# dac.net
KiCad netlist of a schematic drawn in EAGLE
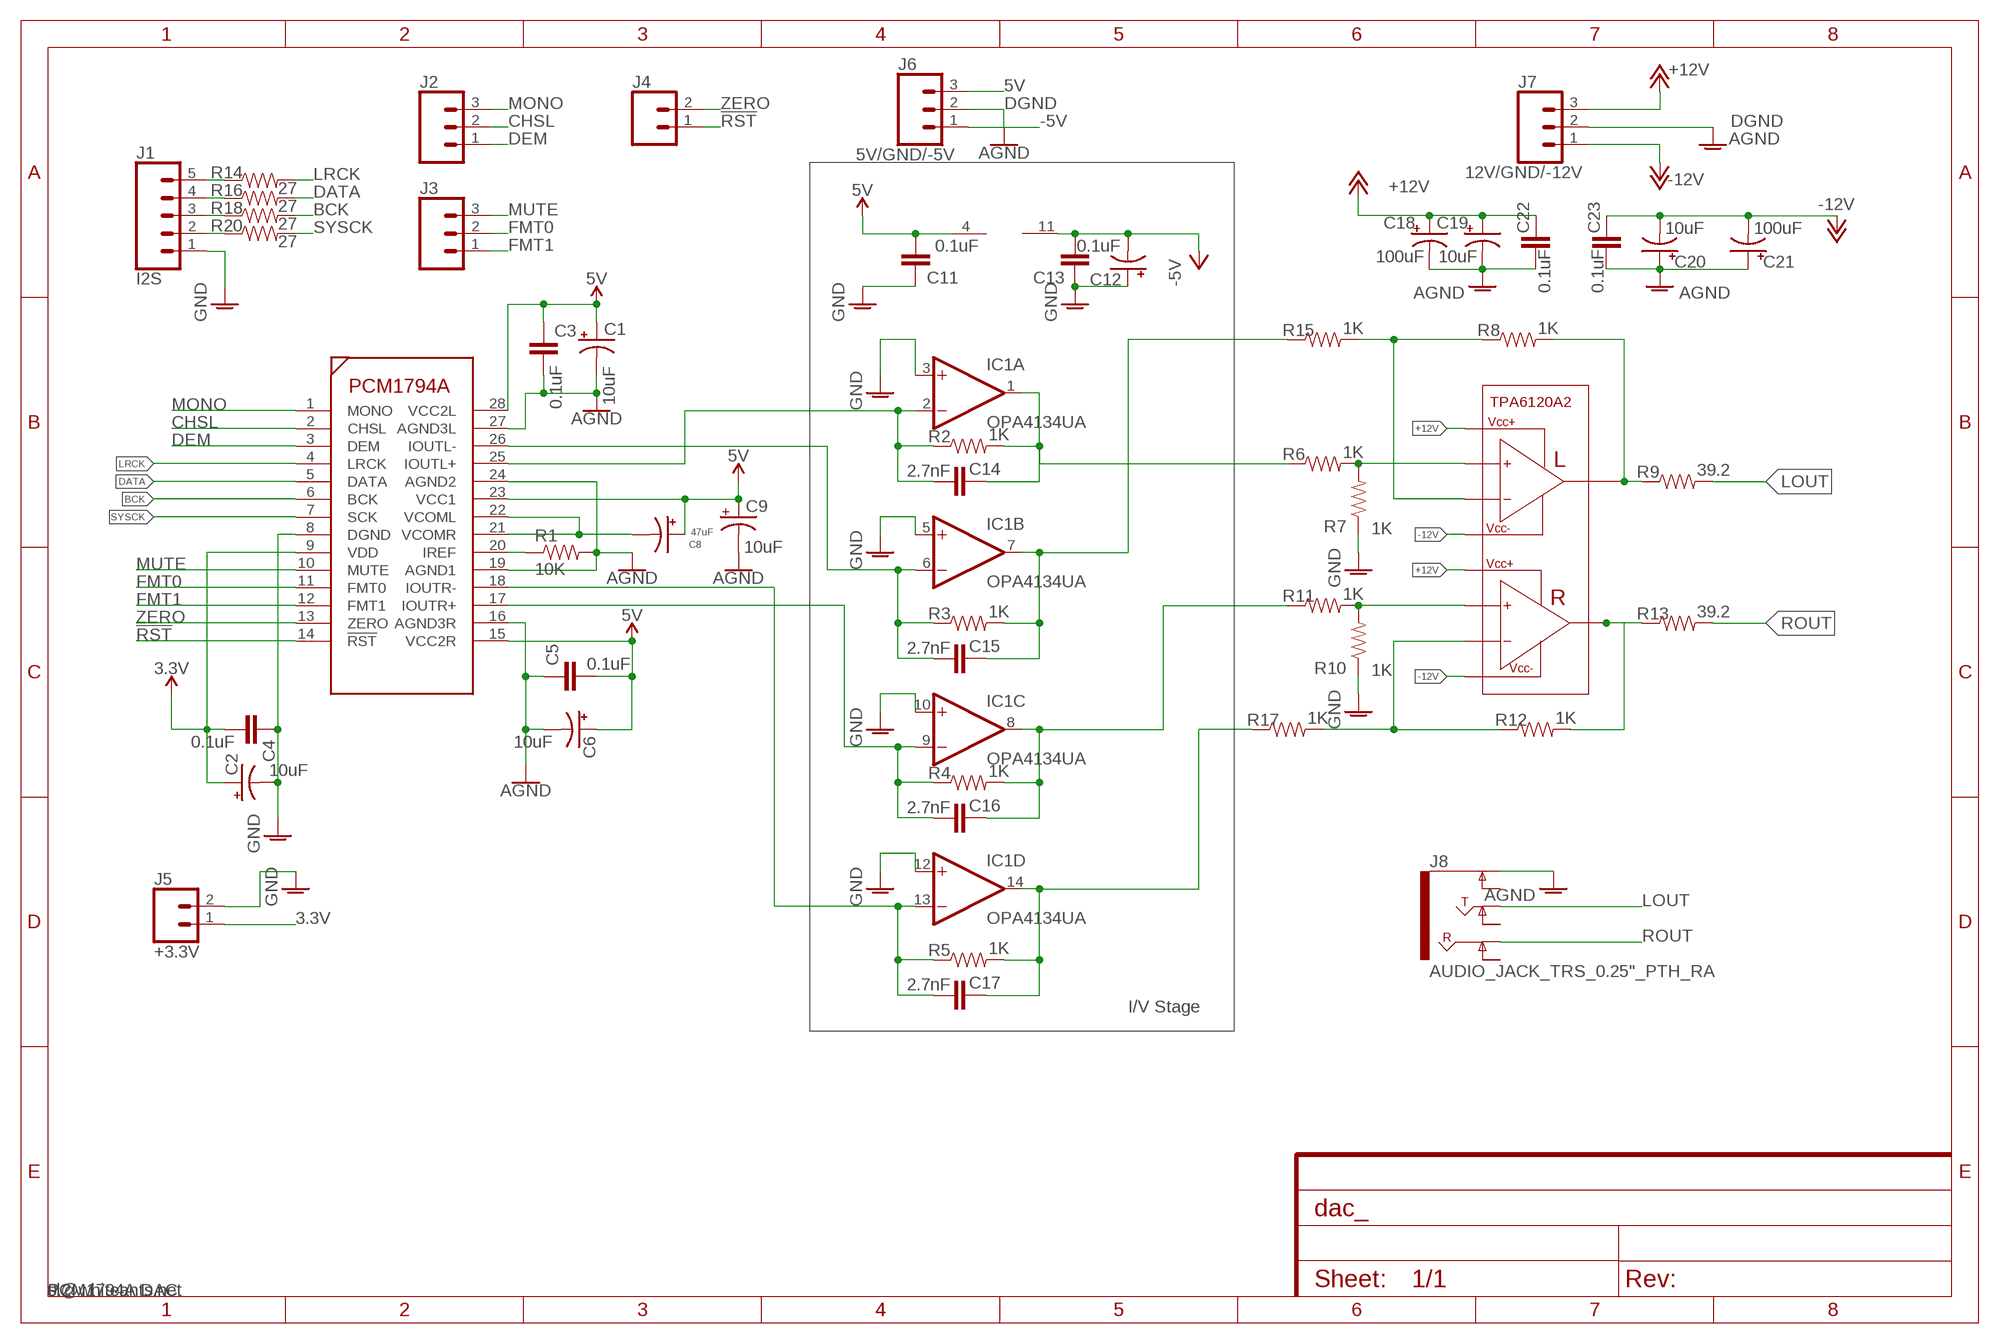
[diagram p0: schematic, sheet 1]

(export (version "E")
  (design (tool "Eeschema 10.0.6"))
  (components
    (comp (ref "C1")
      (value "10uF")
      (footprint "eagle-import:CPOL-RADIAL-100UF-25V")
      (libsource (lib "eagle-import") (part "CAP_POLPTH1"))
    )
    (comp (ref "C2")
      (value "10uF")
      (footprint "eagle-import:CPOL-RADIAL-100UF-25V")
      (libsource (lib "eagle-import") (part "CAP_POLPTH1"))
    )
    (comp (ref "C3")
      (value "0.1uF")
      (footprint "eagle-import:1206")
      (libsource (lib "eagle-import") (part "CAP1206"))
    )
    (comp (ref "C4")
      (value "0.1uF")
      (footprint "eagle-import:1206")
      (libsource (lib "eagle-import") (part "CAP1206"))
    )
    (comp (ref "C5")
      (value "0.1uF")
      (footprint "eagle-import:1206")
      (libsource (lib "eagle-import") (part "CAP1206"))
    )
    (comp (ref "C6")
      (value "10uF")
      (footprint "eagle-import:CPOL-RADIAL-100UF-25V")
      (libsource (lib "eagle-import") (part "CAP_POLPTH1"))
    )
    (comp (ref "C8")
      (value "47uF")
      (footprint "eagle-import:CPOL-RADIAL-100UF-25V")
      (libsource (lib "eagle-import") (part "CAP_POLPTH1"))
    )
    (comp (ref "C9")
      (value "10uF")
      (footprint "eagle-import:CPOL-RADIAL-100UF-25V")
      (libsource (lib "eagle-import") (part "CAP_POLPTH1"))
    )
    (comp (ref "C11")
      (value "0.1uF")
      (footprint "eagle-import:1206")
      (libsource (lib "eagle-import") (part "CAP1206"))
    )
    (comp (ref "C12")
      (value "10uF")
      (footprint "eagle-import:CPOL-RADIAL-100UF-25V")
      (libsource (lib "eagle-import") (part "CAP_POLPTH1"))
    )
    (comp (ref "C13")
      (value "0.1uF")
      (footprint "eagle-import:1206")
      (libsource (lib "eagle-import") (part "CAP1206"))
    )
    (comp (ref "C14")
      (value "2.7nF")
      (footprint "eagle-import:1206")
      (libsource (lib "eagle-import") (part "CAP1206"))
    )
    (comp (ref "C15")
      (value "2.7nF")
      (footprint "eagle-import:1206")
      (libsource (lib "eagle-import") (part "CAP1206"))
    )
    (comp (ref "C16")
      (value "2.7nF")
      (footprint "eagle-import:1206")
      (libsource (lib "eagle-import") (part "CAP1206"))
    )
    (comp (ref "C17")
      (value "2.7nF")
      (footprint "eagle-import:1206")
      (libsource (lib "eagle-import") (part "CAP1206"))
    )
    (comp (ref "C18")
      (value "100uF")
      (footprint "eagle-import:CPOL-RADIAL-100UF-25V")
      (libsource (lib "eagle-import") (part "CAP_POLPTH1"))
    )
    (comp (ref "C19")
      (value "10uF")
      (footprint "eagle-import:CPOL-RADIAL-100UF-25V")
      (libsource (lib "eagle-import") (part "CAP_POLPTH1"))
    )
    (comp (ref "C20")
      (value "10uF")
      (footprint "eagle-import:CPOL-RADIAL-100UF-25V")
      (libsource (lib "eagle-import") (part "CAP_POLPTH1"))
    )
    (comp (ref "C21")
      (value "100uF")
      (footprint "eagle-import:CPOL-RADIAL-100UF-25V")
      (libsource (lib "eagle-import") (part "CAP_POLPTH1"))
    )
    (comp (ref "C22")
      (value "0.1uF")
      (footprint "eagle-import:1206")
      (libsource (lib "eagle-import") (part "CAP1206"))
    )
    (comp (ref "C23")
      (value "0.1uF")
      (footprint "eagle-import:1206")
      (libsource (lib "eagle-import") (part "CAP1206"))
    )
    (comp (ref "IC1")
      (value "OPA4134UA")
      (footprint "eagle-import:SO14")
      (fields (field (name "SPICEPREFIX") "J"))
      (libsource (lib "eagle-import") (part "OPA4UA134"))
    )
    (comp (ref "J1")
      (value "I2S")
      (footprint "eagle-import:1X05")
      (libsource (lib "eagle-import") (part "CONN_05"))
    )
    (comp (ref "J2")
      (value "CONN_03POLAR")
      (footprint "eagle-import:MOLEX-1X3")
      (libsource (lib "eagle-import") (part "CONN_03POLAR"))
    )
    (comp (ref "J3")
      (value "CONN_03POLAR")
      (footprint "eagle-import:MOLEX-1X3")
      (libsource (lib "eagle-import") (part "CONN_03POLAR"))
    )
    (comp (ref "J4")
      (value "CONN_02POLAR_LOCK")
      (footprint "eagle-import:MOLEX-1X2_LOCK")
      (libsource (lib "eagle-import") (part "CONN_02POLAR_LOCK"))
    )
    (comp (ref "J5")
      (value "+3.3V")
      (footprint "eagle-import:MOLEX-1X2")
      (libsource (lib "eagle-import") (part "CONN_02POLAR"))
    )
    (comp (ref "J6")
      (value "5V/GND/-5V")
      (footprint "eagle-import:1X03_LONGPADS")
      (libsource (lib "eagle-import") (part "CONN_03LONGPADS"))
    )
    (comp (ref "J7")
      (value "12V/GND/-12V")
      (footprint "eagle-import:1X03_LONGPADS")
      (libsource (lib "eagle-import") (part "CONN_03LONGPADS"))
    )
    (comp (ref "J8")
      (value "AUDIO_JACK_TRS_0.25\"_PTH_RA")
      (footprint "eagle-import:AUDIO_JACK_0.25__TRS_PTH_RA")
      (libsource (lib "eagle-import") (part "AUDIO_JACK_TRS_0.25{dblquote}_PTH_RA"))
    )
    (comp (ref "R1")
      (value "10K")
      (footprint "eagle-import:0805")
      (libsource (lib "eagle-import") (part "RESISTOR0805-RES"))
    )
    (comp (ref "R2")
      (value "1K")
      (footprint "eagle-import:0805")
      (libsource (lib "eagle-import") (part "RESISTOR0805-RES"))
    )
    (comp (ref "R3")
      (value "1K")
      (footprint "eagle-import:0805")
      (libsource (lib "eagle-import") (part "RESISTOR0805-RES"))
    )
    (comp (ref "R4")
      (value "1K")
      (footprint "eagle-import:0805")
      (libsource (lib "eagle-import") (part "RESISTOR0805-RES"))
    )
    (comp (ref "R5")
      (value "1K")
      (footprint "eagle-import:0805")
      (libsource (lib "eagle-import") (part "RESISTOR0805-RES"))
    )
    (comp (ref "R6")
      (value "1K")
      (footprint "eagle-import:0805")
      (libsource (lib "eagle-import") (part "RESISTOR0805-RES"))
    )
    (comp (ref "R7")
      (value "1K")
      (footprint "eagle-import:0805")
      (libsource (lib "eagle-import") (part "RESISTOR0805-RES"))
    )
    (comp (ref "R8")
      (value "1K")
      (footprint "eagle-import:0805")
      (libsource (lib "eagle-import") (part "RESISTOR0805-RES"))
    )
    (comp (ref "R9")
      (value "39.2")
      (footprint "eagle-import:0805")
      (libsource (lib "eagle-import") (part "RESISTOR0805-RES"))
    )
    (comp (ref "R10")
      (value "1K")
      (footprint "eagle-import:0805")
      (libsource (lib "eagle-import") (part "RESISTOR0805-RES"))
    )
    (comp (ref "R11")
      (value "1K")
      (footprint "eagle-import:0805")
      (libsource (lib "eagle-import") (part "RESISTOR0805-RES"))
    )
    (comp (ref "R12")
      (value "1K")
      (footprint "eagle-import:0805")
      (libsource (lib "eagle-import") (part "RESISTOR0805-RES"))
    )
    (comp (ref "R13")
      (value "39.2")
      (footprint "eagle-import:0805")
      (libsource (lib "eagle-import") (part "RESISTOR0805-RES"))
    )
    (comp (ref "R14")
      (value "27")
      (footprint "eagle-import:0805")
      (libsource (lib "eagle-import") (part "RESISTOR0805-RES"))
    )
    (comp (ref "R15")
      (value "1K")
      (footprint "eagle-import:0805")
      (libsource (lib "eagle-import") (part "RESISTOR0805-RES"))
    )
    (comp (ref "R16")
      (value "27")
      (footprint "eagle-import:0805")
      (libsource (lib "eagle-import") (part "RESISTOR0805-RES"))
    )
    (comp (ref "R17")
      (value "1K")
      (footprint "eagle-import:0805")
      (libsource (lib "eagle-import") (part "RESISTOR0805-RES"))
    )
    (comp (ref "R18")
      (value "27")
      (footprint "eagle-import:0805")
      (libsource (lib "eagle-import") (part "RESISTOR0805-RES"))
    )
    (comp (ref "R20")
      (value "27")
      (footprint "eagle-import:0805")
      (libsource (lib "eagle-import") (part "RESISTOR0805-RES"))
    )
    (comp (ref "UK1")
      (value "PCM1794A")
      (footprint "eagle-import:SSOP28-0.65-10.2X5.2MM")
      (libsource (lib "eagle-import") (part "PCM1794A"))
    )
    (comp (ref "UK2")
      (value "TPA6120A2")
      (footprint "eagle-import:SOIC20S")
      (libsource (lib "eagle-import") (part "TPA6120A2"))
    )
  )
  (nets
    (net (code "1") (name "+12V") (class "Default")
      (node (ref "C18") (pin "1") (pinfunction "+_1") (pintype "passive"))
      (node (ref "C19") (pin "1") (pinfunction "+_1") (pintype "passive"))
      (node (ref "C22") (pin "1") (pinfunction "1_1") (pintype "passive"))
      (node (ref "J7") (pin "3") (pinfunction "3_3") (pintype "passive"))
      (node (ref "UK2") (pin "18") (pinfunction "RVCC+_18") (pintype "power_in"))
      (node (ref "UK2") (pin "3") (pinfunction "LVCC+_3") (pintype "bidirectional"))
    )
    (net (code "2") (name "-5V") (class "Default")
      (node (ref "C12") (pin "2") (pinfunction "-_2") (pintype "passive"))
      (node (ref "C13") (pin "2") (pinfunction "2_2") (pintype "passive"))
      (node (ref "IC1") (pin "11") (pinfunction "V-_11") (pintype "power_in"))
      (node (ref "J6") (pin "1") (pinfunction "1_1") (pintype "passive"))
    )
    (net (code "3") (name "-12V") (class "Default")
      (node (ref "C20") (pin "2") (pinfunction "-_2") (pintype "passive"))
      (node (ref "C21") (pin "2") (pinfunction "-_2") (pintype "passive"))
      (node (ref "C23") (pin "1") (pinfunction "1_1") (pintype "passive"))
      (node (ref "J7") (pin "1") (pinfunction "1_1") (pintype "passive"))
      (node (ref "UK2") (pin "1") (pinfunction "LVCC-_1") (pintype "power_in"))
      (node (ref "UK2") (pin "20") (pinfunction "RVCC-_20") (pintype "power_in"))
    )
    (net (code "4") (name "/CHSL") (class "Default")
      (node (ref "J2") (pin "2") (pinfunction "2_2") (pintype "passive"))
      (node (ref "UK1") (pin "2") (pinfunction "CHSL_2") (pintype "bidirectional"))
    )
    (net (code "5") (name "/DEM") (class "Default")
      (node (ref "J2") (pin "1") (pinfunction "1_1") (pintype "passive"))
      (node (ref "UK1") (pin "3") (pinfunction "DEM_3") (pintype "bidirectional"))
    )
    (net (code "6") (name "/FMT0") (class "Default")
      (node (ref "J3") (pin "2") (pinfunction "2_2") (pintype "passive"))
      (node (ref "UK1") (pin "11") (pinfunction "FMT0_11") (pintype "bidirectional"))
    )
    (net (code "7") (name "/FMT1") (class "Default")
      (node (ref "J3") (pin "1") (pinfunction "1_1") (pintype "passive"))
      (node (ref "UK1") (pin "12") (pinfunction "FMT1_12") (pintype "bidirectional"))
    )
    (net (code "8") (name "/MONO") (class "Default")
      (node (ref "J2") (pin "3") (pinfunction "3_3") (pintype "passive"))
      (node (ref "UK1") (pin "1") (pinfunction "MONO_1") (pintype "bidirectional"))
    )
    (net (code "9") (name "/MUTE") (class "Default")
      (node (ref "J3") (pin "3") (pinfunction "3_3") (pintype "passive"))
      (node (ref "UK1") (pin "10") (pinfunction "MUTE_10") (pintype "bidirectional"))
    )
    (net (code "10") (name "/ZERO") (class "Default")
      (node (ref "J4") (pin "2") (pinfunction "2_2") (pintype "passive"))
      (node (ref "UK1") (pin "13") (pinfunction "ZERO_13") (pintype "bidirectional"))
    )
    (net (code "11") (name "/~{RST}") (class "Default")
      (node (ref "J4") (pin "1") (pinfunction "1_1") (pintype "passive"))
      (node (ref "UK1") (pin "14") (pinfunction "~{RST}_14") (pintype "bidirectional"))
    )
    (net (code "12") (name "3.3V") (class "Default")
      (node (ref "C2") (pin "1") (pinfunction "+_1") (pintype "passive"))
      (node (ref "C4") (pin "2") (pinfunction "2_2") (pintype "passive"))
      (node (ref "J5") (pin "1") (pinfunction "1_1") (pintype "passive"))
      (node (ref "UK1") (pin "9") (pinfunction "VDD_9") (pintype "bidirectional"))
    )
    (net (code "13") (name "5V") (class "Default")
      (node (ref "C1") (pin "1") (pinfunction "+_1") (pintype "passive"))
      (node (ref "C11") (pin "2") (pinfunction "2_2") (pintype "passive"))
      (node (ref "C3") (pin "1") (pinfunction "1_1") (pintype "passive"))
      (node (ref "C5") (pin "2") (pinfunction "2_2") (pintype "passive"))
      (node (ref "C6") (pin "1") (pinfunction "+_1") (pintype "passive"))
      (node (ref "C8") (pin "1") (pinfunction "+_1") (pintype "passive"))
      (node (ref "C9") (pin "1") (pinfunction "+_1") (pintype "passive"))
      (node (ref "IC1") (pin "4") (pinfunction "V+_4") (pintype "power_in"))
      (node (ref "J6") (pin "3") (pinfunction "3_3") (pintype "passive"))
      (node (ref "UK1") (pin "15") (pinfunction "VCC2R_15") (pintype "bidirectional"))
      (node (ref "UK1") (pin "23") (pinfunction "VCC1_23") (pintype "bidirectional"))
      (node (ref "UK1") (pin "28") (pinfunction "VCC2L_28") (pintype "bidirectional"))
    )
    (net (code "14") (name "AGND") (class "Default")
      (node (ref "C1") (pin "2") (pinfunction "-_2") (pintype "passive"))
      (node (ref "C11") (pin "1") (pinfunction "1_1") (pintype "passive"))
      (node (ref "C12") (pin "1") (pinfunction "+_1") (pintype "passive"))
      (node (ref "C13") (pin "1") (pinfunction "1_1") (pintype "passive"))
      (node (ref "C18") (pin "2") (pinfunction "-_2") (pintype "passive"))
      (node (ref "C19") (pin "2") (pinfunction "-_2") (pintype "passive"))
      (node (ref "C2") (pin "2") (pinfunction "-_2") (pintype "passive"))
      (node (ref "C20") (pin "1") (pinfunction "+_1") (pintype "passive"))
      (node (ref "C21") (pin "1") (pinfunction "+_1") (pintype "passive"))
      (node (ref "C22") (pin "2") (pinfunction "2_2") (pintype "passive"))
      (node (ref "C23") (pin "2") (pinfunction "2_2") (pintype "passive"))
      (node (ref "C3") (pin "2") (pinfunction "2_2") (pintype "passive"))
      (node (ref "C4") (pin "1") (pinfunction "1_1") (pintype "passive"))
      (node (ref "C5") (pin "1") (pinfunction "1_1") (pintype "passive"))
      (node (ref "C6") (pin "2") (pinfunction "-_2") (pintype "passive"))
      (node (ref "C9") (pin "2") (pinfunction "-_2") (pintype "passive"))
      (node (ref "IC1") (pin "10") (pinfunction "+IN_10") (pintype "input"))
      (node (ref "IC1") (pin "12") (pinfunction "+IN_12") (pintype "input"))
      (node (ref "IC1") (pin "3") (pinfunction "+IN_3") (pintype "input"))
      (node (ref "IC1") (pin "5") (pinfunction "+IN_5") (pintype "input"))
      (node (ref "J1") (pin "1") (pinfunction "1_1") (pintype "passive"))
      (node (ref "J5") (pin "2") (pinfunction "2_2") (pintype "passive"))
      (node (ref "J6") (pin "2") (pinfunction "2_2") (pintype "passive"))
      (node (ref "J7") (pin "2") (pinfunction "2_2") (pintype "passive"))
      (node (ref "J8") (pin "SLEEVE") (pinfunction "EARTH_SLEEVE") (pintype "bidirectional"))
      (node (ref "R1") (pin "2") (pinfunction "2_2") (pintype "passive"))
      (node (ref "R10") (pin "1") (pinfunction "1_1") (pintype "passive"))
      (node (ref "R7") (pin "1") (pinfunction "1_1") (pintype "passive"))
      (node (ref "UK1") (pin "16") (pinfunction "AGND3R_16") (pintype "bidirectional"))
      (node (ref "UK1") (pin "19") (pinfunction "AGND1_19") (pintype "bidirectional"))
      (node (ref "UK1") (pin "24") (pinfunction "AGND2_24") (pintype "bidirectional"))
      (node (ref "UK1") (pin "27") (pinfunction "AGND3L_27") (pintype "bidirectional"))
      (node (ref "UK1") (pin "8") (pinfunction "DGND_8") (pintype "bidirectional"))
    )
    (net (code "15") (name "BCK") (class "Default")
      (node (ref "R18") (pin "2") (pinfunction "2_2") (pintype "passive"))
      (node (ref "UK1") (pin "6") (pinfunction "BCK_6") (pintype "bidirectional"))
    )
    (net (code "16") (name "DATA") (class "Default")
      (node (ref "R16") (pin "2") (pinfunction "2_2") (pintype "passive"))
      (node (ref "UK1") (pin "5") (pinfunction "DATA_5") (pintype "bidirectional"))
    )
    (net (code "17") (name "LOUT") (class "Default")
      (node (ref "J8") (pin "TIP") (pinfunction "TIP_TIP") (pintype "bidirectional"))
      (node (ref "R9") (pin "2") (pinfunction "2_2") (pintype "passive"))
    )
    (net (code "18") (name "LRCK") (class "Default")
      (node (ref "R14") (pin "2") (pinfunction "2_2") (pintype "passive"))
      (node (ref "UK1") (pin "4") (pinfunction "LRCK_4") (pintype "bidirectional"))
    )
    (net (code "19") (name "Net-(C8--)") (class "Default")
      (node (ref "C8") (pin "2") (pinfunction "-_2") (pintype "passive"))
      (node (ref "UK1") (pin "21") (pinfunction "VCOMR_21") (pintype "bidirectional"))
      (node (ref "UK1") (pin "22") (pinfunction "VCOML_22") (pintype "bidirectional"))
    )
    (net (code "20") (name "Net-(IC1A--IN)") (class "Default")
      (node (ref "C14") (pin "2") (pinfunction "2_2") (pintype "passive"))
      (node (ref "IC1") (pin "2") (pinfunction "-IN_2") (pintype "input"))
      (node (ref "R2") (pin "1") (pinfunction "1_1") (pintype "passive"))
      (node (ref "UK1") (pin "25") (pinfunction "IOUTL+_25") (pintype "bidirectional"))
    )
    (net (code "21") (name "Net-(IC1A-OUT)") (class "Default")
      (node (ref "C14") (pin "1") (pinfunction "1_1") (pintype "passive"))
      (node (ref "IC1") (pin "1") (pinfunction "OUT_1") (pintype "output"))
      (node (ref "R2") (pin "2") (pinfunction "2_2") (pintype "passive"))
      (node (ref "R6") (pin "1") (pinfunction "1_1") (pintype "passive"))
    )
    (net (code "22") (name "Net-(IC1B--IN)") (class "Default")
      (node (ref "C15") (pin "2") (pinfunction "2_2") (pintype "passive"))
      (node (ref "IC1") (pin "6") (pinfunction "-IN_6") (pintype "input"))
      (node (ref "R3") (pin "1") (pinfunction "1_1") (pintype "passive"))
      (node (ref "UK1") (pin "26") (pinfunction "IOUTL-_26") (pintype "bidirectional"))
    )
    (net (code "23") (name "Net-(IC1B-OUT)") (class "Default")
      (node (ref "C15") (pin "1") (pinfunction "1_1") (pintype "passive"))
      (node (ref "IC1") (pin "7") (pinfunction "OUT_7") (pintype "output"))
      (node (ref "R15") (pin "1") (pinfunction "1_1") (pintype "passive"))
      (node (ref "R3") (pin "2") (pinfunction "2_2") (pintype "passive"))
    )
    (net (code "24") (name "Net-(IC1C--IN)") (class "Default")
      (node (ref "C16") (pin "2") (pinfunction "2_2") (pintype "passive"))
      (node (ref "IC1") (pin "9") (pinfunction "-IN_9") (pintype "input"))
      (node (ref "R4") (pin "1") (pinfunction "1_1") (pintype "passive"))
      (node (ref "UK1") (pin "17") (pinfunction "IOUTR+_17") (pintype "bidirectional"))
    )
    (net (code "25") (name "Net-(IC1C-OUT)") (class "Default")
      (node (ref "C16") (pin "1") (pinfunction "1_1") (pintype "passive"))
      (node (ref "IC1") (pin "8") (pinfunction "OUT_8") (pintype "output"))
      (node (ref "R11") (pin "1") (pinfunction "1_1") (pintype "passive"))
      (node (ref "R4") (pin "2") (pinfunction "2_2") (pintype "passive"))
    )
    (net (code "26") (name "Net-(IC1D--IN)") (class "Default")
      (node (ref "C17") (pin "2") (pinfunction "2_2") (pintype "passive"))
      (node (ref "IC1") (pin "13") (pinfunction "-IN_13") (pintype "input"))
      (node (ref "R5") (pin "1") (pinfunction "1_1") (pintype "passive"))
      (node (ref "UK1") (pin "18") (pinfunction "IOUTR-_18") (pintype "bidirectional"))
    )
    (net (code "27") (name "Net-(IC1D-OUT)") (class "Default")
      (node (ref "C17") (pin "1") (pinfunction "1_1") (pintype "passive"))
      (node (ref "IC1") (pin "14") (pinfunction "OUT_14") (pintype "output"))
      (node (ref "R17") (pin "1") (pinfunction "1_1") (pintype "passive"))
      (node (ref "R5") (pin "2") (pinfunction "2_2") (pintype "passive"))
    )
    (net (code "28") (name "Net-(J1-Pad2)") (class "Default")
      (node (ref "J1") (pin "2") (pinfunction "2_2") (pintype "passive"))
      (node (ref "R20") (pin "1") (pinfunction "1_1") (pintype "passive"))
    )
    (net (code "29") (name "Net-(J1-Pad3)") (class "Default")
      (node (ref "J1") (pin "3") (pinfunction "3_3") (pintype "passive"))
      (node (ref "R18") (pin "1") (pinfunction "1_1") (pintype "passive"))
    )
    (net (code "30") (name "Net-(J1-Pad4)") (class "Default")
      (node (ref "J1") (pin "4") (pinfunction "4_4") (pintype "passive"))
      (node (ref "R16") (pin "1") (pinfunction "1_1") (pintype "passive"))
    )
    (net (code "31") (name "Net-(J1-Pad5)") (class "Default")
      (node (ref "J1") (pin "5") (pinfunction "5_5") (pintype "passive"))
      (node (ref "R14") (pin "1") (pinfunction "1_1") (pintype "passive"))
    )
    (net (code "32") (name "Net-(UK1-IREF)") (class "Default")
      (node (ref "R1") (pin "1") (pinfunction "1_1") (pintype "passive"))
      (node (ref "UK1") (pin "20") (pinfunction "IREF_20") (pintype "bidirectional"))
    )
    (net (code "33") (name "Net-(UK2-LIN+)") (class "Default")
      (node (ref "R6") (pin "2") (pinfunction "2_2") (pintype "passive"))
      (node (ref "R7") (pin "2") (pinfunction "2_2") (pintype "passive"))
      (node (ref "UK2") (pin "4") (pinfunction "LIN+_4") (pintype "input"))
    )
    (net (code "34") (name "Net-(UK2-LIN-)") (class "Default")
      (node (ref "R15") (pin "2") (pinfunction "2_2") (pintype "passive"))
      (node (ref "R8") (pin "1") (pinfunction "1_1") (pintype "passive"))
      (node (ref "UK2") (pin "5") (pinfunction "LIN-_5") (pintype "input"))
    )
    (net (code "35") (name "Net-(UK2-LOUT)") (class "Default")
      (node (ref "R8") (pin "2") (pinfunction "2_2") (pintype "passive"))
      (node (ref "R9") (pin "1") (pinfunction "1_1") (pintype "passive"))
      (node (ref "UK2") (pin "2") (pinfunction "LOUT_2") (pintype "output"))
    )
    (net (code "36") (name "Net-(UK2-RIN+)") (class "Default")
      (node (ref "R10") (pin "2") (pinfunction "2_2") (pintype "passive"))
      (node (ref "R11") (pin "2") (pinfunction "2_2") (pintype "passive"))
      (node (ref "UK2") (pin "17") (pinfunction "RIN+_17") (pintype "input"))
    )
    (net (code "37") (name "Net-(UK2-RIN-)") (class "Default")
      (node (ref "R12") (pin "1") (pinfunction "1_1") (pintype "passive"))
      (node (ref "R17") (pin "2") (pinfunction "2_2") (pintype "passive"))
      (node (ref "UK2") (pin "16") (pinfunction "RIN-_16") (pintype "input"))
    )
    (net (code "38") (name "Net-(UK2-ROUT)") (class "Default")
      (node (ref "R12") (pin "2") (pinfunction "2_2") (pintype "passive"))
      (node (ref "R13") (pin "1") (pinfunction "1_1") (pintype "passive"))
      (node (ref "UK2") (pin "19") (pinfunction "ROUT_19") (pintype "output"))
    )
    (net (code "39") (name "ROUT") (class "Default")
      (node (ref "J8") (pin "RING") (pinfunction "RING_RING") (pintype "bidirectional"))
      (node (ref "R13") (pin "2") (pinfunction "2_2") (pintype "passive"))
    )
    (net (code "40") (name "SYSCK") (class "Default")
      (node (ref "R20") (pin "2") (pinfunction "2_2") (pintype "passive"))
      (node (ref "UK1") (pin "7") (pinfunction "SCK_7") (pintype "bidirectional"))
    )
    (net (code "41") (name "unconnected-(J8-EARTH-NORM-PadSLEEVE-NORM)") (class "Default")
      (node (ref "J8") (pin "SLEEVE-NORM") (pinfunction "EARTH-NORM_SLEEVE-NORM") (pintype "bidirectional"))
    )
    (net (code "42") (name "unconnected-(J8-PadRING-NORM)") (class "Default")
      (node (ref "J8") (pin "RING-NORM") (pinfunction "RING-NORM_RING-NORM") (pintype "bidirectional"))
    )
    (net (code "43") (name "unconnected-(J8-PadTIP-NORM)") (class "Default")
      (node (ref "J8") (pin "TIP-NORM") (pinfunction "TIP-NORM_TIP-NORM") (pintype "bidirectional"))
    )
  )
)
